# blueimu.net
KiCad netlist of a schematic drawn in EAGLE
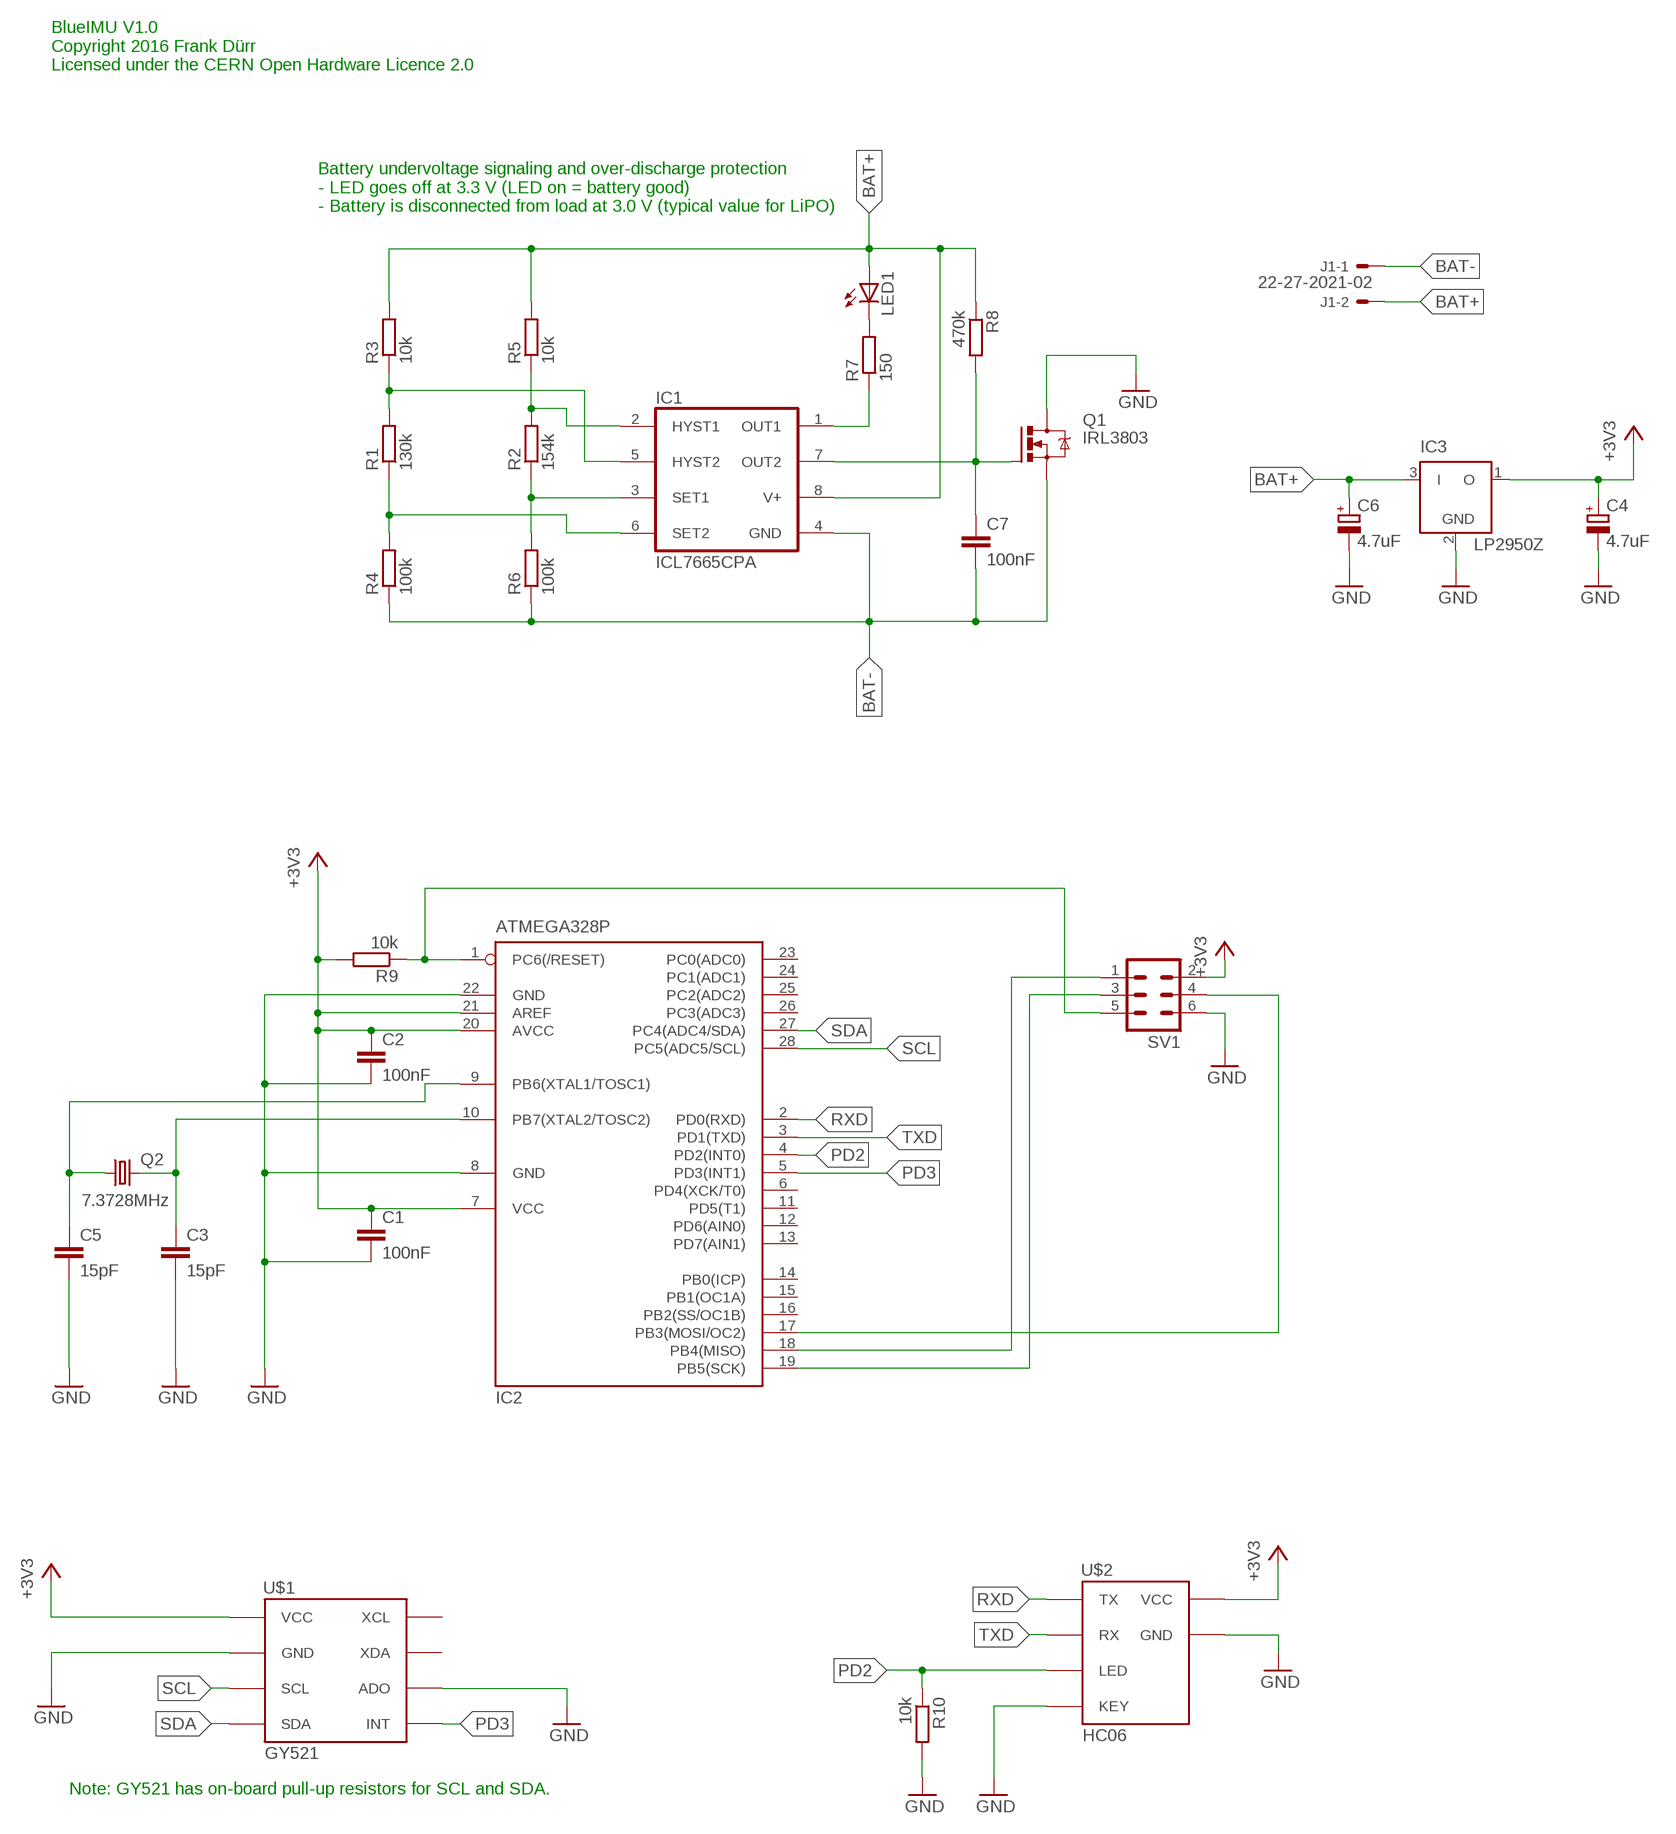
[diagram p0: schematic, sheet 1]

(export (version "E")
  (design (tool "Eeschema 10.0.6"))
  (components
    (comp (ref "C1")
      (value "100nF")
      (footprint "eagle-import:C050-024X044")
      (libsource (lib "eagle-import") (part "C-EU050-024X044"))
    )
    (comp (ref "C2")
      (value "100nF")
      (footprint "eagle-import:C050-024X044")
      (libsource (lib "eagle-import") (part "C-EU050-024X044"))
    )
    (comp (ref "C3")
      (value "15pF")
      (footprint "eagle-import:C025-025X050")
      (libsource (lib "eagle-import") (part "C-EU025-025X050"))
    )
    (comp (ref "C4")
      (value "4.7uF")
      (footprint "eagle-import:E2,5-5")
      (libsource (lib "eagle-import") (part "CPOL-EUE2.5-5"))
    )
    (comp (ref "C5")
      (value "15pF")
      (footprint "eagle-import:C025-025X050")
      (libsource (lib "eagle-import") (part "C-EU025-025X050"))
    )
    (comp (ref "C6")
      (value "4.7uF")
      (footprint "eagle-import:E2,5-5")
      (libsource (lib "eagle-import") (part "CPOL-EUE2.5-5"))
    )
    (comp (ref "C7")
      (value "100nF")
      (footprint "eagle-import:C050-024X044")
      (libsource (lib "eagle-import") (part "C-EU050-024X044"))
    )
    (comp (ref "IC1")
      (value "ICL7665CPA")
      (footprint "eagle-import:DIL08")
      (libsource (lib "eagle-import") (part "ICL7665CPA"))
    )
    (comp (ref "IC2")
      (value "ATMEGA328P")
      (footprint "eagle-import:DIL28-3")
      (libsource (lib "eagle-import") (part "MEGA8-P"))
    )
    (comp (ref "IC3")
      (value "LP2950Z")
      (footprint "eagle-import:TO92")
      (libsource (lib "eagle-import") (part "LP2950Z"))
    )
    (comp (ref "J1")
      (value "22-27-2021-02")
      (footprint "eagle-import:6410-02")
      (libsource (lib "eagle-import") (part "22-?-0227-2021"))
    )
    (comp (ref "LED1")
      (value "LED3MM")
      (footprint "eagle-import:LED3MM")
      (libsource (lib "eagle-import") (part "LED3MM"))
    )
    (comp (ref "Q1")
      (value "IRL3803")
      (footprint "eagle-import:TO220BV")
      (libsource (lib "eagle-import") (part "IRF520"))
    )
    (comp (ref "Q2")
      (value "7.3728MHz")
      (footprint "eagle-import:HC49U-V")
      (libsource (lib "eagle-import") (part "CRYSTALHC49U-V"))
    )
    (comp (ref "R1")
      (value "130k")
      (footprint "eagle-import:0207_7")
      (libsource (lib "eagle-import") (part "R-EU_0207/7"))
    )
    (comp (ref "R2")
      (value "154k")
      (footprint "eagle-import:0207_7")
      (libsource (lib "eagle-import") (part "R-EU_0207/7"))
    )
    (comp (ref "R3")
      (value "10k")
      (footprint "eagle-import:0207_7")
      (libsource (lib "eagle-import") (part "R-EU_0207/7"))
    )
    (comp (ref "R4")
      (value "100k")
      (footprint "eagle-import:0207_7")
      (libsource (lib "eagle-import") (part "R-EU_0207/7"))
    )
    (comp (ref "R5")
      (value "10k")
      (footprint "eagle-import:0207_7")
      (libsource (lib "eagle-import") (part "R-EU_0207/7"))
    )
    (comp (ref "R6")
      (value "100k")
      (footprint "eagle-import:0207_7")
      (libsource (lib "eagle-import") (part "R-EU_0207/7"))
    )
    (comp (ref "R7")
      (value "150")
      (footprint "eagle-import:0207_7")
      (libsource (lib "eagle-import") (part "R-EU_0207/7"))
    )
    (comp (ref "R8")
      (value "470k")
      (footprint "eagle-import:0207_7")
      (libsource (lib "eagle-import") (part "R-EU_0207/7"))
    )
    (comp (ref "R9")
      (value "10k")
      (footprint "eagle-import:0207_7")
      (libsource (lib "eagle-import") (part "R-EU_0207/7"))
    )
    (comp (ref "R10")
      (value "10k")
      (footprint "eagle-import:0207_7")
      (libsource (lib "eagle-import") (part "R-EU_0207/7"))
    )
    (comp (ref "SV1")
      (value "MA03-2")
      (footprint "eagle-import:MA03-2")
      (libsource (lib "eagle-import") (part "MA03-2"))
    )
    (comp (ref "U$1")
      (value "GY521")
      (footprint "eagle-import:GY521")
      (libsource (lib "eagle-import") (part "GY521"))
    )
    (comp (ref "U$2")
      (value "HC06")
      (footprint "eagle-import:HC06")
      (libsource (lib "eagle-import") (part "HC06"))
    )
  )
  (nets
    (net (code "1") (name "+3V3") (class "Default")
      (node (ref "C1") (pin "1") (pinfunction "1_1") (pintype "passive"))
      (node (ref "C2") (pin "1") (pinfunction "1_1") (pintype "passive"))
      (node (ref "C4") (pin "+") (pinfunction "+_+") (pintype "passive"))
      (node (ref "IC2") (pin "20") (pinfunction "AVCC_20") (pintype "power_in"))
      (node (ref "IC2") (pin "21") (pinfunction "AREF_21") (pintype "passive"))
      (node (ref "IC2") (pin "7") (pinfunction "VCC_7") (pintype "power_in"))
      (node (ref "IC3") (pin "1") (pinfunction "O_1") (pintype "input"))
      (node (ref "R9") (pin "2") (pinfunction "2_2") (pintype "passive"))
      (node (ref "SV1") (pin "2") (pinfunction "2_2") (pintype "passive"))
      (node (ref "U$1") (pin "VCC") (pinfunction "VCC_VCC") (pintype "power_in"))
      (node (ref "U$2") (pin "VCC") (pinfunction "VCC_VCC") (pintype "power_in"))
    )
    (net (code "2") (name "BAT+") (class "Default")
      (node (ref "C6") (pin "+") (pinfunction "+_+") (pintype "passive"))
      (node (ref "IC1") (pin "8") (pinfunction "V+_8") (pintype "power_in"))
      (node (ref "IC3") (pin "3") (pinfunction "I_3") (pintype "input"))
      (node (ref "J1") (pin "2") (pinfunction "S_2") (pintype "passive"))
      (node (ref "LED1") (pin "A") (pinfunction "A_A") (pintype "passive"))
      (node (ref "R3") (pin "2") (pinfunction "2_2") (pintype "passive"))
      (node (ref "R5") (pin "2") (pinfunction "2_2") (pintype "passive"))
      (node (ref "R8") (pin "1") (pinfunction "1_1") (pintype "passive"))
    )
    (net (code "3") (name "BAT-") (class "Default")
      (node (ref "C7") (pin "2") (pinfunction "2_2") (pintype "passive"))
      (node (ref "IC1") (pin "4") (pinfunction "GND_4") (pintype "power_in"))
      (node (ref "J1") (pin "1") (pinfunction "S_1") (pintype "passive"))
      (node (ref "Q1") (pin "S") (pinfunction "S_S") (pintype "passive"))
      (node (ref "R4") (pin "1") (pinfunction "1_1") (pintype "passive"))
      (node (ref "R6") (pin "1") (pinfunction "1_1") (pintype "passive"))
    )
    (net (code "4") (name "GND") (class "Default")
      (node (ref "C1") (pin "2") (pinfunction "2_2") (pintype "passive"))
      (node (ref "C2") (pin "2") (pinfunction "2_2") (pintype "passive"))
      (node (ref "C3") (pin "2") (pinfunction "2_2") (pintype "passive"))
      (node (ref "C4") (pin "-") (pinfunction "-_-") (pintype "passive"))
      (node (ref "C5") (pin "2") (pinfunction "2_2") (pintype "passive"))
      (node (ref "C6") (pin "-") (pinfunction "-_-") (pintype "passive"))
      (node (ref "IC2") (pin "22") (pinfunction "GND_22") (pintype "power_in"))
      (node (ref "IC2") (pin "8") (pinfunction "GND_8") (pintype "power_in"))
      (node (ref "IC3") (pin "2") (pinfunction "GND_2") (pintype "power_in"))
      (node (ref "Q1") (pin "D") (pinfunction "D_D") (pintype "passive"))
      (node (ref "R10") (pin "2") (pinfunction "2_2") (pintype "passive"))
      (node (ref "SV1") (pin "6") (pinfunction "6_6") (pintype "passive"))
      (node (ref "U$1") (pin "ADO") (pinfunction "ADO_ADO") (pintype "input"))
      (node (ref "U$1") (pin "GND") (pinfunction "GND_GND") (pintype "power_in"))
      (node (ref "U$2") (pin "GND") (pinfunction "GND_GND") (pintype "power_in"))
      (node (ref "U$2") (pin "KEY") (pinfunction "KEY_KEY") (pintype "input"))
    )
    (net (code "5") (name "Net-(IC1-HYST1)") (class "Default")
      (node (ref "IC1") (pin "2") (pinfunction "HYST1_2") (pintype "input"))
      (node (ref "R2") (pin "2") (pinfunction "2_2") (pintype "passive"))
      (node (ref "R5") (pin "1") (pinfunction "1_1") (pintype "passive"))
    )
    (net (code "6") (name "Net-(IC1-HYST2)") (class "Default")
      (node (ref "IC1") (pin "5") (pinfunction "HYST2_5") (pintype "input"))
      (node (ref "R1") (pin "2") (pinfunction "2_2") (pintype "passive"))
      (node (ref "R3") (pin "1") (pinfunction "1_1") (pintype "passive"))
    )
    (net (code "7") (name "Net-(IC1-OUT1)") (class "Default")
      (node (ref "IC1") (pin "1") (pinfunction "OUT1_1") (pintype "output"))
      (node (ref "R7") (pin "1") (pinfunction "1_1") (pintype "passive"))
    )
    (net (code "8") (name "Net-(IC1-OUT2)") (class "Default")
      (node (ref "C7") (pin "1") (pinfunction "1_1") (pintype "passive"))
      (node (ref "IC1") (pin "7") (pinfunction "OUT2_7") (pintype "output"))
      (node (ref "Q1") (pin "G") (pinfunction "G_G") (pintype "passive"))
      (node (ref "R8") (pin "2") (pinfunction "2_2") (pintype "passive"))
    )
    (net (code "9") (name "Net-(IC1-SET1)") (class "Default")
      (node (ref "IC1") (pin "3") (pinfunction "SET1_3") (pintype "input"))
      (node (ref "R2") (pin "1") (pinfunction "1_1") (pintype "passive"))
      (node (ref "R6") (pin "2") (pinfunction "2_2") (pintype "passive"))
    )
    (net (code "10") (name "Net-(IC1-SET2)") (class "Default")
      (node (ref "IC1") (pin "6") (pinfunction "SET2_6") (pintype "input"))
      (node (ref "R1") (pin "1") (pinfunction "1_1") (pintype "passive"))
      (node (ref "R4") (pin "2") (pinfunction "2_2") (pintype "passive"))
    )
    (net (code "11") (name "Net-(IC2-PB3(MOSI{slash}OC2))") (class "Default")
      (node (ref "IC2") (pin "17") (pinfunction "PB3(MOSI/OC2)_17") (pintype "bidirectional"))
      (node (ref "SV1") (pin "4") (pinfunction "4_4") (pintype "passive"))
    )
    (net (code "12") (name "Net-(IC2-PB4(MISO))") (class "Default")
      (node (ref "IC2") (pin "18") (pinfunction "PB4(MISO)_18") (pintype "bidirectional"))
      (node (ref "SV1") (pin "1") (pinfunction "1_1") (pintype "passive"))
    )
    (net (code "13") (name "Net-(IC2-PB5(SCK))") (class "Default")
      (node (ref "IC2") (pin "19") (pinfunction "PB5(SCK)_19") (pintype "bidirectional"))
      (node (ref "SV1") (pin "3") (pinfunction "3_3") (pintype "passive"))
    )
    (net (code "14") (name "Net-(IC2-PB6(XTAL1{slash}TOSC1))") (class "Default")
      (node (ref "C5") (pin "1") (pinfunction "1_1") (pintype "passive"))
      (node (ref "IC2") (pin "9") (pinfunction "PB6(XTAL1/TOSC1)_9") (pintype "bidirectional"))
      (node (ref "Q2") (pin "1") (pinfunction "1_1") (pintype "passive"))
    )
    (net (code "15") (name "Net-(IC2-PB7(XTAL2{slash}TOSC2))") (class "Default")
      (node (ref "C3") (pin "1") (pinfunction "1_1") (pintype "passive"))
      (node (ref "IC2") (pin "10") (pinfunction "PB7(XTAL2/TOSC2)_10") (pintype "bidirectional"))
      (node (ref "Q2") (pin "2") (pinfunction "2_2") (pintype "passive"))
    )
    (net (code "16") (name "Net-(IC2-PC6({slash}RESET))") (class "Default")
      (node (ref "IC2") (pin "1") (pinfunction "PC6(/RESET)_1") (pintype "bidirectional"))
      (node (ref "R9") (pin "1") (pinfunction "1_1") (pintype "passive"))
      (node (ref "SV1") (pin "5") (pinfunction "5_5") (pintype "passive"))
    )
    (net (code "17") (name "Net-(LED1-C)") (class "Default")
      (node (ref "LED1") (pin "K") (pinfunction "C_K") (pintype "passive"))
      (node (ref "R7") (pin "2") (pinfunction "2_2") (pintype "passive"))
    )
    (net (code "18") (name "PD2") (class "Default")
      (node (ref "IC2") (pin "4") (pinfunction "PD2(INT0)_4") (pintype "bidirectional"))
      (node (ref "R10") (pin "1") (pinfunction "1_1") (pintype "passive"))
      (node (ref "U$2") (pin "LED") (pinfunction "LED_LED") (pintype "output"))
    )
    (net (code "19") (name "PD3") (class "Default")
      (node (ref "IC2") (pin "5") (pinfunction "PD3(INT1)_5") (pintype "bidirectional"))
      (node (ref "U$1") (pin "INT") (pinfunction "INT_INT") (pintype "output"))
    )
    (net (code "20") (name "RXD") (class "Default")
      (node (ref "IC2") (pin "2") (pinfunction "PD0(RXD)_2") (pintype "bidirectional"))
      (node (ref "U$2") (pin "TX") (pinfunction "TX_TX") (pintype "output"))
    )
    (net (code "21") (name "SCL") (class "Default")
      (node (ref "IC2") (pin "28") (pinfunction "PC5(ADC5/SCL)_28") (pintype "bidirectional"))
      (node (ref "U$1") (pin "SCL") (pinfunction "SCL_SCL") (pintype "input"))
    )
    (net (code "22") (name "SDA") (class "Default")
      (node (ref "IC2") (pin "27") (pinfunction "PC4(ADC4/SDA)_27") (pintype "bidirectional"))
      (node (ref "U$1") (pin "SDA") (pinfunction "SDA_SDA") (pintype "bidirectional"))
    )
    (net (code "23") (name "TXD") (class "Default")
      (node (ref "IC2") (pin "3") (pinfunction "PD1(TXD)_3") (pintype "bidirectional"))
      (node (ref "U$2") (pin "RX") (pinfunction "RX_RX") (pintype "bidirectional"))
    )
    (net (code "24") (name "unconnected-(IC2-PB0(ICP)-Pad14)") (class "Default")
      (node (ref "IC2") (pin "14") (pinfunction "PB0(ICP)_14") (pintype "bidirectional"))
    )
    (net (code "25") (name "unconnected-(IC2-PB1(OC1A)-Pad15)") (class "Default")
      (node (ref "IC2") (pin "15") (pinfunction "PB1(OC1A)_15") (pintype "bidirectional"))
    )
    (net (code "26") (name "unconnected-(IC2-PB2(SS{slash}OC1B)-Pad16)") (class "Default")
      (node (ref "IC2") (pin "16") (pinfunction "PB2(SS/OC1B)_16") (pintype "bidirectional"))
    )
    (net (code "27") (name "unconnected-(IC2-PC0(ADC0)-Pad23)") (class "Default")
      (node (ref "IC2") (pin "23") (pinfunction "PC0(ADC0)_23") (pintype "bidirectional"))
    )
    (net (code "28") (name "unconnected-(IC2-PC1(ADC1)-Pad24)") (class "Default")
      (node (ref "IC2") (pin "24") (pinfunction "PC1(ADC1)_24") (pintype "bidirectional"))
    )
    (net (code "29") (name "unconnected-(IC2-PC2(ADC2)-Pad25)") (class "Default")
      (node (ref "IC2") (pin "25") (pinfunction "PC2(ADC2)_25") (pintype "bidirectional"))
    )
    (net (code "30") (name "unconnected-(IC2-PC3(ADC3)-Pad26)") (class "Default")
      (node (ref "IC2") (pin "26") (pinfunction "PC3(ADC3)_26") (pintype "bidirectional"))
    )
    (net (code "31") (name "unconnected-(IC2-PD4(XCK{slash}T0)-Pad6)") (class "Default")
      (node (ref "IC2") (pin "6") (pinfunction "PD4(XCK/T0)_6") (pintype "bidirectional"))
    )
    (net (code "32") (name "unconnected-(IC2-PD5(T1)-Pad11)") (class "Default")
      (node (ref "IC2") (pin "11") (pinfunction "PD5(T1)_11") (pintype "bidirectional"))
    )
    (net (code "33") (name "unconnected-(IC2-PD6(AIN0)-Pad12)") (class "Default")
      (node (ref "IC2") (pin "12") (pinfunction "PD6(AIN0)_12") (pintype "bidirectional"))
    )
    (net (code "34") (name "unconnected-(IC2-PD7(AIN1)-Pad13)") (class "Default")
      (node (ref "IC2") (pin "13") (pinfunction "PD7(AIN1)_13") (pintype "bidirectional"))
    )
    (net (code "35") (name "unconnected-(U$1-PadXCL)") (class "Default")
      (node (ref "U$1") (pin "XCL") (pinfunction "XCL_XCL") (pintype "output"))
    )
    (net (code "36") (name "unconnected-(U$1-PadXDA)") (class "Default")
      (node (ref "U$1") (pin "XDA") (pinfunction "XDA_XDA") (pintype "bidirectional"))
    )
  )
)
